# scanimage-bias.net
KiCad netlist of a schematic drawn in EAGLE
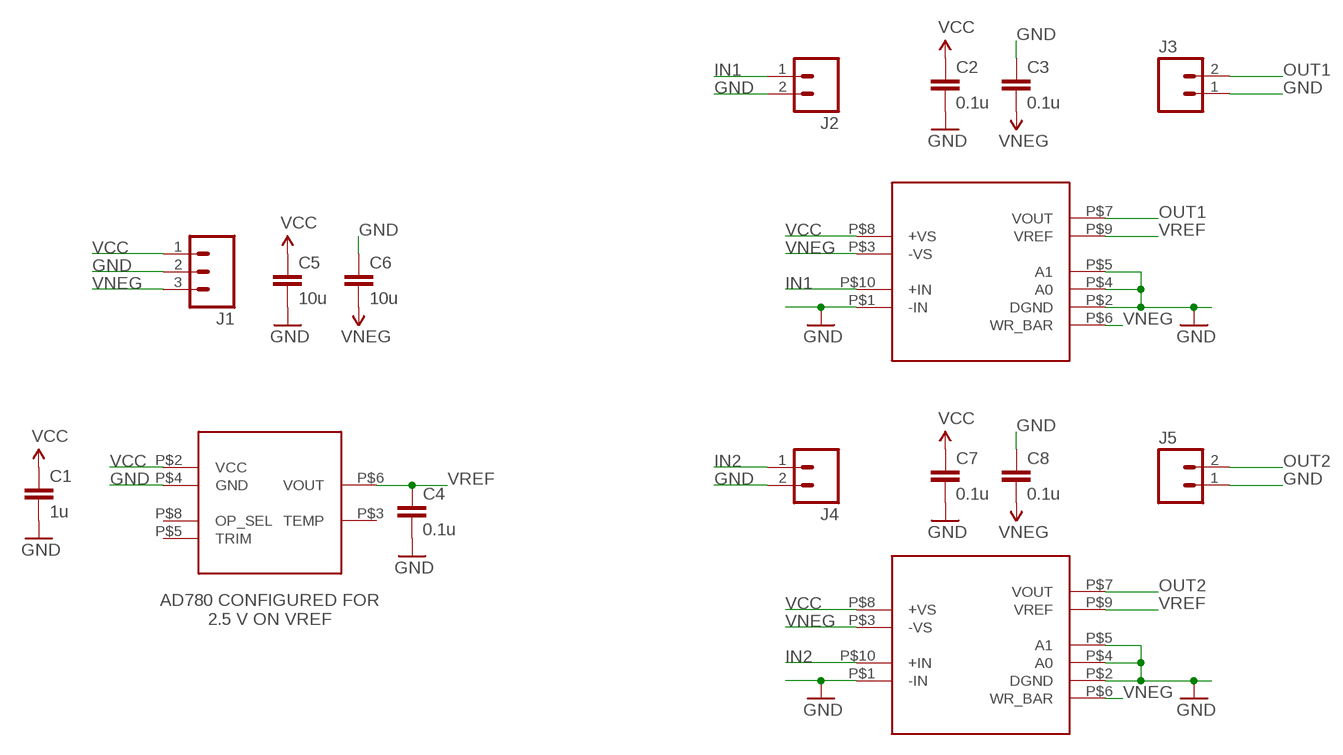
[diagram p0: schematic, sheet 1]

(export (version "E")
  (design (tool "Eeschema 10.0.6"))
  (components
    (comp (ref "C1")
      (value "1u")
      (footprint "eagle-import:1206")
      (libsource (lib "eagle-import") (part "CAP1206"))
    )
    (comp (ref "C2")
      (value "0.1u")
      (footprint "eagle-import:1206")
      (libsource (lib "eagle-import") (part "CAP1206"))
    )
    (comp (ref "C3")
      (value "0.1u")
      (footprint "eagle-import:1206")
      (libsource (lib "eagle-import") (part "CAP1206"))
    )
    (comp (ref "C4")
      (value "0.1u")
      (footprint "eagle-import:1206")
      (libsource (lib "eagle-import") (part "CAP1206"))
    )
    (comp (ref "C5")
      (value "10u")
      (footprint "eagle-import:1206")
      (libsource (lib "eagle-import") (part "CAP1206"))
    )
    (comp (ref "C6")
      (value "10u")
      (footprint "eagle-import:1206")
      (libsource (lib "eagle-import") (part "CAP1206"))
    )
    (comp (ref "C7")
      (value "0.1u")
      (footprint "eagle-import:1206")
      (libsource (lib "eagle-import") (part "CAP1206"))
    )
    (comp (ref "C8")
      (value "0.1u")
      (footprint "eagle-import:1206")
      (libsource (lib "eagle-import") (part "CAP1206"))
    )
    (comp (ref "J1")
      (value "M03PTH")
      (footprint "eagle-import:1X03")
      (libsource (lib "eagle-import") (part "M03PTH"))
    )
    (comp (ref "J2")
      (value "M02PTH")
      (footprint "eagle-import:1X02")
      (libsource (lib "eagle-import") (part "M02PTH"))
    )
    (comp (ref "J3")
      (value "M02PTH")
      (footprint "eagle-import:1X02")
      (libsource (lib "eagle-import") (part "M02PTH"))
    )
    (comp (ref "J4")
      (value "M02PTH")
      (footprint "eagle-import:1X02")
      (libsource (lib "eagle-import") (part "M02PTH"))
    )
    (comp (ref "J5")
      (value "M02PTH")
      (footprint "eagle-import:1X02")
      (libsource (lib "eagle-import") (part "M02PTH"))
    )
    (comp (ref "U$1")
      (value "AD780")
      (footprint "eagle-import:SOIC-8")
      (libsource (lib "eagle-import") (part "AD780"))
    )
    (comp (ref "U$2")
      (value "AD8250")
      (footprint "eagle-import:MSOP-10")
      (libsource (lib "eagle-import") (part "AD8250"))
    )
    (comp (ref "U$3")
      (value "AD8250")
      (footprint "eagle-import:MSOP-10")
      (libsource (lib "eagle-import") (part "AD8250"))
    )
  )
  (nets
    (net (code "1") (name "/IN1") (class "Default")
      (node (ref "J2") (pin "1") (pinfunction "1_1") (pintype "passive"))
      (node (ref "U$2") (pin "P$10") (pinfunction "+IN_P$10") (pintype "bidirectional"))
    )
    (net (code "2") (name "/IN2") (class "Default")
      (node (ref "J4") (pin "1") (pinfunction "1_1") (pintype "passive"))
      (node (ref "U$3") (pin "P$10") (pinfunction "+IN_P$10") (pintype "bidirectional"))
    )
    (net (code "3") (name "/OUT1") (class "Default")
      (node (ref "J3") (pin "2") (pinfunction "2_2") (pintype "passive"))
      (node (ref "U$2") (pin "P$7") (pinfunction "VOUT_P$7") (pintype "bidirectional"))
    )
    (net (code "4") (name "/OUT2") (class "Default")
      (node (ref "J5") (pin "2") (pinfunction "2_2") (pintype "passive"))
      (node (ref "U$3") (pin "P$7") (pinfunction "VOUT_P$7") (pintype "bidirectional"))
    )
    (net (code "5") (name "/VREF") (class "Default")
      (node (ref "C4") (pin "1") (pinfunction "1_1") (pintype "passive"))
      (node (ref "U$1") (pin "P$6") (pinfunction "VOUT_P$6") (pintype "bidirectional"))
      (node (ref "U$2") (pin "P$9") (pinfunction "VREF_P$9") (pintype "bidirectional"))
      (node (ref "U$3") (pin "P$9") (pinfunction "VREF_P$9") (pintype "bidirectional"))
    )
    (net (code "6") (name "GND") (class "Default")
      (node (ref "C1") (pin "2") (pinfunction "2_2") (pintype "passive"))
      (node (ref "C2") (pin "2") (pinfunction "2_2") (pintype "passive"))
      (node (ref "C3") (pin "1") (pinfunction "1_1") (pintype "passive"))
      (node (ref "C4") (pin "2") (pinfunction "2_2") (pintype "passive"))
      (node (ref "C5") (pin "2") (pinfunction "2_2") (pintype "passive"))
      (node (ref "C6") (pin "1") (pinfunction "1_1") (pintype "passive"))
      (node (ref "C7") (pin "2") (pinfunction "2_2") (pintype "passive"))
      (node (ref "C8") (pin "1") (pinfunction "1_1") (pintype "passive"))
      (node (ref "J1") (pin "2") (pinfunction "2_2") (pintype "passive"))
      (node (ref "J2") (pin "2") (pinfunction "2_2") (pintype "passive"))
      (node (ref "J3") (pin "1") (pinfunction "1_1") (pintype "passive"))
      (node (ref "J4") (pin "2") (pinfunction "2_2") (pintype "passive"))
      (node (ref "J5") (pin "1") (pinfunction "1_1") (pintype "passive"))
      (node (ref "U$1") (pin "P$4") (pinfunction "GND_P$4") (pintype "bidirectional"))
      (node (ref "U$2") (pin "P$1") (pinfunction "-IN_P$1") (pintype "bidirectional"))
      (node (ref "U$2") (pin "P$2") (pinfunction "DGND_P$2") (pintype "bidirectional"))
      (node (ref "U$2") (pin "P$4") (pinfunction "A0_P$4") (pintype "bidirectional"))
      (node (ref "U$2") (pin "P$5") (pinfunction "A1_P$5") (pintype "bidirectional"))
      (node (ref "U$3") (pin "P$1") (pinfunction "-IN_P$1") (pintype "bidirectional"))
      (node (ref "U$3") (pin "P$2") (pinfunction "DGND_P$2") (pintype "bidirectional"))
      (node (ref "U$3") (pin "P$4") (pinfunction "A0_P$4") (pintype "bidirectional"))
      (node (ref "U$3") (pin "P$5") (pinfunction "A1_P$5") (pintype "bidirectional"))
    )
    (net (code "7") (name "VCC") (class "Default")
      (node (ref "C1") (pin "1") (pinfunction "1_1") (pintype "passive"))
      (node (ref "C2") (pin "1") (pinfunction "1_1") (pintype "passive"))
      (node (ref "C5") (pin "1") (pinfunction "1_1") (pintype "passive"))
      (node (ref "C7") (pin "1") (pinfunction "1_1") (pintype "passive"))
      (node (ref "J1") (pin "1") (pinfunction "1_1") (pintype "passive"))
      (node (ref "U$1") (pin "P$2") (pinfunction "VCC_P$2") (pintype "bidirectional"))
      (node (ref "U$2") (pin "P$8") (pinfunction "+VS_P$8") (pintype "bidirectional"))
      (node (ref "U$3") (pin "P$8") (pinfunction "+VS_P$8") (pintype "bidirectional"))
    )
    (net (code "8") (name "VNEG") (class "Default")
      (node (ref "C3") (pin "2") (pinfunction "2_2") (pintype "passive"))
      (node (ref "C6") (pin "2") (pinfunction "2_2") (pintype "passive"))
      (node (ref "C8") (pin "2") (pinfunction "2_2") (pintype "passive"))
      (node (ref "J1") (pin "3") (pinfunction "3_3") (pintype "passive"))
      (node (ref "U$2") (pin "P$3") (pinfunction "-VS_P$3") (pintype "bidirectional"))
      (node (ref "U$2") (pin "P$6") (pinfunction "WR_BAR_P$6") (pintype "bidirectional"))
      (node (ref "U$3") (pin "P$3") (pinfunction "-VS_P$3") (pintype "bidirectional"))
      (node (ref "U$3") (pin "P$6") (pinfunction "WR_BAR_P$6") (pintype "bidirectional"))
    )
    (net (code "9") (name "unconnected-(U$1-OP_SEL-PadP$8)") (class "Default")
      (node (ref "U$1") (pin "P$8") (pinfunction "OP_SEL_P$8") (pintype "bidirectional"))
    )
    (net (code "10") (name "unconnected-(U$1-TEMP-PadP$3)") (class "Default")
      (node (ref "U$1") (pin "P$3") (pinfunction "TEMP_P$3") (pintype "bidirectional"))
    )
    (net (code "11") (name "unconnected-(U$1-TRIM-PadP$5)") (class "Default")
      (node (ref "U$1") (pin "P$5") (pinfunction "TRIM_P$5") (pintype "bidirectional"))
    )
  )
)
